# design.net
KiCad netlist of a schematic drawn in Altium Designer
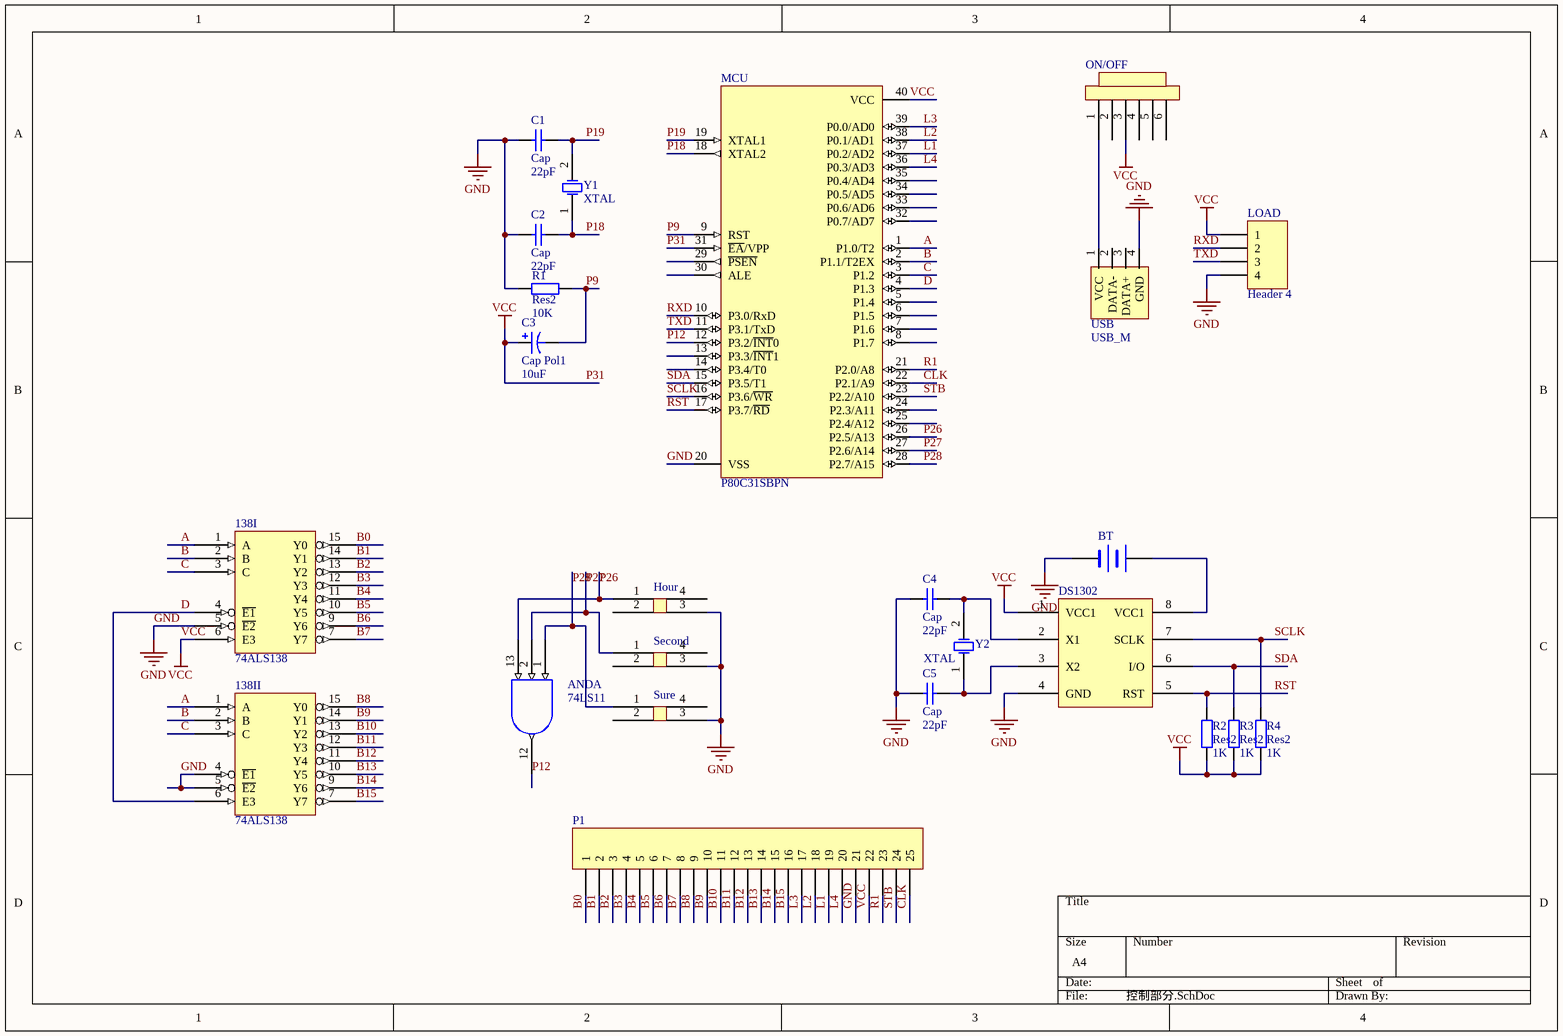
[diagram p0: 控制部分.SchDoc]

(export (version "E")
  (design (tool "Eeschema 10.0.6"))
  (components
    (comp (ref "138I")
      (value "74ALS138")
      (footprint "DIP-16")
      (libsource (lib "TTL74系列IC") (part "74ALS138"))
    )
    (comp (ref "138II")
      (value "74ALS138")
      (footprint "DIP-16")
      (libsource (lib "TTL74系列IC") (part "74ALS138"))
    )
    (comp (ref "AND") (value "74LS11") (footprint "DIP-14") (libsource (lib "TTL74系列IC") (part "74LS11")))
    (comp (ref "BT")
      (value "~")
      (footprint "纽扣电池:PCBComponent_1")
      (description "Battery")
      (libsource (lib "电池及电源") (part "干电池"))
    )
    (comp (ref "C1")
      (value "Cap")
      (footprint "Miscellaneous Connectors:HDR1X2")
      (description "Capacitor")
      (fields (field (name "ALTIUM_VALUE") "22pF") (field (name "PUBLISHER") "Altium Limited"))
      (libsource (lib "Miscellaneous Devices") (part "Cap"))
    )
    (comp (ref "C2")
      (value "Cap")
      (footprint "Miscellaneous Connectors:HDR1X2")
      (description "Capacitor")
      (fields (field (name "ALTIUM_VALUE") "22pF") (field (name "PUBLISHER") "Altium Limited"))
      (libsource (lib "Miscellaneous Devices") (part "Cap"))
    )
    (comp (ref "C3")
      (value "Cap Pol1")
      (footprint "单片机最小系统:LED")
      (description "Polarized Capacitor (Radial)")
      (fields (field (name "ALTIUM_VALUE") "10uF") (field (name "PUBLISHER") "Altium Limited"))
      (libsource (lib "Miscellaneous Devices") (part "Cap Pol1"))
    )
    (comp (ref "C4")
      (value "Cap")
      (footprint "PIN2")
      (description "Capacitor")
      (fields (field (name "ALTIUM_VALUE") "22pF") (field (name "PUBLISHER") "Altium Limited"))
      (libsource (lib "Miscellaneous Devices") (part "Cap"))
    )
    (comp (ref "C5")
      (value "Cap")
      (footprint "PIN2")
      (description "Capacitor")
      (fields (field (name "ALTIUM_VALUE") "22pF") (field (name "PUBLISHER") "Altium Limited"))
      (libsource (lib "Miscellaneous Devices") (part "Cap"))
    )
    (comp (ref "DS1302") (value "~") (footprint "DIP8") (libsource (lib "DS1302") (part "Component_1")))
    (comp (ref "Hour")
      (value "~")
      (footprint "按键1:PCBComponent_1")
      (libsource (lib "按键1") (part "Component_1"))
    )
    (comp (ref "LOAD")
      (value "Header 4")
      (footprint "HDR1X4")
      (description "Header, 4-Pin")
      (fields (field (name "PUBLISHER") "Altium Limited"))
      (libsource (lib "Miscellaneous Connectors") (part "Header 4"))
    )
    (comp (ref "MCU")
      (value "P80C31SBPN")
      (footprint "SOT129-1")
      (description "80C51 8-Bit Microcontroller Family: 128 B RAM, ROMless, 2.7 V-5.5 V, Low Power, High Speed")
      (fields (field (name "PUBLISHER") "Altium Limited"))
      (libsource (lib "Philips Microcontroller 8-Bit") (part "P80C31SBPN"))
    )
    (comp (ref "ON/OFF") (value "~") (footprint "复位开关:PCBComponent_1") (libsource (lib "复位开关") (part "复位开关")))
    (comp (ref "P1")
      (value "~")
      (footprint "HDR1X25")
      (description "Header, 25-Pin")
      (fields (field (name "PUBLISHER") "Altium Limited"))
      (libsource (lib "Miscellaneous Connectors") (part "Header 25"))
    )
    (comp (ref "R1")
      (value "Res2")
      (footprint "AXIAL-0.4")
      (description "Resistor")
      (fields (field (name "ALTIUM_VALUE") "10K") (field (name "PUBLISHER") "Altium Limited"))
      (libsource (lib "Miscellaneous Devices") (part "Res2"))
    )
    (comp (ref "R2")
      (value "Res2")
      (footprint "AXIAL-0.4")
      (description "Resistor")
      (fields (field (name "ALTIUM_VALUE") "1K") (field (name "PUBLISHER") "Altium Limited"))
      (libsource (lib "") (part "Res2_1"))
    )
    (comp (ref "R3")
      (value "Res2")
      (footprint "AXIAL-0.4")
      (description "Resistor")
      (fields (field (name "ALTIUM_VALUE") "1K") (field (name "PUBLISHER") "Altium Limited"))
      (libsource (lib "") (part "Res2_1"))
    )
    (comp (ref "R4")
      (value "Res2")
      (footprint "AXIAL-0.4")
      (description "Resistor")
      (fields (field (name "ALTIUM_VALUE") "1K") (field (name "PUBLISHER") "Altium Limited"))
      (libsource (lib "") (part "Res2_1"))
    )
    (comp (ref "Second")
      (value "~")
      (footprint "按键1:PCBComponent_1")
      (libsource (lib "按键1") (part "Component_1"))
    )
    (comp (ref "Sure")
      (value "~")
      (footprint "按键1:PCBComponent_1")
      (libsource (lib "按键1") (part "Component_1"))
    )
    (comp (ref "USB") (value "USB_M") (footprint "USB") (libsource (lib "SCH封装库") (part "USB_M")))
    (comp (ref "Y1")
      (value "XTAL")
      (footprint "晶振:PCBComponent_1")
      (description "Crystal Oscillator")
      (fields (field (name "PUBLISHER") "Altium Limited"))
      (libsource (lib "Miscellaneous Devices") (part "XTAL"))
    )
    (comp (ref "Y2")
      (value "XTAL")
      (footprint "HDR1X2")
      (description "Crystal Oscillator")
      (fields (field (name "PUBLISHER") "Altium Limited"))
      (libsource (lib "Miscellaneous Devices") (part "XTAL"))
    )
  )
  (nets
    (net (code "1") (name "/A") (class "Default")
      (node (ref "138I") (pin "1") (pinfunction "A_1") (pintype "input"))
      (node (ref "138II") (pin "1") (pinfunction "A_1") (pintype "input"))
      (node (ref "MCU") (pin "1") (pinfunction "P1.0/T2_1") (pintype "bidirectional"))
    )
    (net (code "2") (name "/B") (class "Default")
      (node (ref "138I") (pin "2") (pinfunction "B_2") (pintype "input"))
      (node (ref "138II") (pin "2") (pinfunction "B_2") (pintype "input"))
      (node (ref "MCU") (pin "2") (pinfunction "P1.1/T2EX_2") (pintype "bidirectional"))
    )
    (net (code "3") (name "/B0") (class "Default")
      (node (ref "138I") (pin "15") (pinfunction "Y0_15") (pintype "output"))
      (node (ref "P1") (pin "1") (pinfunction "1_1") (pintype "passive"))
    )
    (net (code "4") (name "/B1") (class "Default")
      (node (ref "138I") (pin "14") (pinfunction "Y1_14") (pintype "output"))
      (node (ref "P1") (pin "2") (pinfunction "2_2") (pintype "passive"))
    )
    (net (code "5") (name "/B2") (class "Default")
      (node (ref "138I") (pin "13") (pinfunction "Y2_13") (pintype "output"))
      (node (ref "P1") (pin "3") (pinfunction "3_3") (pintype "passive"))
    )
    (net (code "6") (name "/B3") (class "Default")
      (node (ref "138I") (pin "12") (pinfunction "Y3_12") (pintype "output"))
      (node (ref "P1") (pin "4") (pinfunction "4_4") (pintype "passive"))
    )
    (net (code "7") (name "/B4") (class "Default")
      (node (ref "138I") (pin "11") (pinfunction "Y4_11") (pintype "output"))
      (node (ref "P1") (pin "5") (pinfunction "5_5") (pintype "passive"))
    )
    (net (code "8") (name "/B5") (class "Default")
      (node (ref "138I") (pin "10") (pinfunction "Y5_10") (pintype "output"))
      (node (ref "P1") (pin "6") (pinfunction "6_6") (pintype "passive"))
    )
    (net (code "9") (name "/B6") (class "Default")
      (node (ref "138I") (pin "9") (pinfunction "Y6_9") (pintype "output"))
      (node (ref "P1") (pin "7") (pinfunction "7_7") (pintype "passive"))
    )
    (net (code "10") (name "/B7") (class "Default")
      (node (ref "138I") (pin "7") (pinfunction "Y7_7") (pintype "output"))
      (node (ref "P1") (pin "8") (pinfunction "8_8") (pintype "passive"))
    )
    (net (code "11") (name "/B8") (class "Default")
      (node (ref "138II") (pin "15") (pinfunction "Y0_15") (pintype "output"))
      (node (ref "P1") (pin "9") (pinfunction "9_9") (pintype "passive"))
    )
    (net (code "12") (name "/B9") (class "Default")
      (node (ref "138II") (pin "14") (pinfunction "Y1_14") (pintype "output"))
      (node (ref "P1") (pin "10") (pinfunction "10_10") (pintype "passive"))
    )
    (net (code "13") (name "/B10") (class "Default")
      (node (ref "138II") (pin "13") (pinfunction "Y2_13") (pintype "output"))
      (node (ref "P1") (pin "11") (pinfunction "11_11") (pintype "passive"))
    )
    (net (code "14") (name "/B11") (class "Default")
      (node (ref "138II") (pin "12") (pinfunction "Y3_12") (pintype "output"))
      (node (ref "P1") (pin "12") (pinfunction "12_12") (pintype "passive"))
    )
    (net (code "15") (name "/B12") (class "Default")
      (node (ref "138II") (pin "11") (pinfunction "Y4_11") (pintype "output"))
      (node (ref "P1") (pin "13") (pinfunction "13_13") (pintype "passive"))
    )
    (net (code "16") (name "/B13") (class "Default")
      (node (ref "138II") (pin "10") (pinfunction "Y5_10") (pintype "output"))
      (node (ref "P1") (pin "14") (pinfunction "14_14") (pintype "passive"))
    )
    (net (code "17") (name "/B14") (class "Default")
      (node (ref "138II") (pin "9") (pinfunction "Y6_9") (pintype "output"))
      (node (ref "P1") (pin "15") (pinfunction "15_15") (pintype "passive"))
    )
    (net (code "18") (name "/B15") (class "Default")
      (node (ref "138II") (pin "7") (pinfunction "Y7_7") (pintype "output"))
      (node (ref "P1") (pin "16") (pinfunction "16_16") (pintype "passive"))
    )
    (net (code "19") (name "/C") (class "Default")
      (node (ref "138I") (pin "3") (pinfunction "C_3") (pintype "input"))
      (node (ref "138II") (pin "3") (pinfunction "C_3") (pintype "input"))
      (node (ref "MCU") (pin "3") (pinfunction "P1.2_3") (pintype "bidirectional"))
    )
    (net (code "20") (name "/CLK") (class "Default")
      (node (ref "MCU") (pin "22") (pinfunction "P2.1/A9_22") (pintype "bidirectional"))
      (node (ref "P1") (pin "25") (pinfunction "25_25") (pintype "passive"))
    )
    (net (code "21") (name "/D") (class "Default")
      (node (ref "138I") (pin "4") (pinfunction "~{E1}_4") (pintype "input"))
      (node (ref "138II") (pin "6") (pinfunction "E3_6") (pintype "input"))
      (node (ref "MCU") (pin "4") (pinfunction "P1.3_4") (pintype "bidirectional"))
    )
    (net (code "22") (name "/L1") (class "Default")
      (node (ref "MCU") (pin "37") (pinfunction "P0.2/AD2_37") (pintype "bidirectional"))
      (node (ref "P1") (pin "19") (pinfunction "19_19") (pintype "passive"))
    )
    (net (code "23") (name "/L2") (class "Default")
      (node (ref "MCU") (pin "38") (pinfunction "P0.1/AD1_38") (pintype "bidirectional"))
      (node (ref "P1") (pin "18") (pinfunction "18_18") (pintype "passive"))
    )
    (net (code "24") (name "/L3") (class "Default")
      (node (ref "MCU") (pin "39") (pinfunction "P0.0/AD0_39") (pintype "bidirectional"))
      (node (ref "P1") (pin "17") (pinfunction "17_17") (pintype "passive"))
    )
    (net (code "25") (name "/L4") (class "Default")
      (node (ref "MCU") (pin "36") (pinfunction "P0.3/AD3_36") (pintype "bidirectional"))
      (node (ref "P1") (pin "20") (pinfunction "20_20") (pintype "passive"))
    )
    (net (code "26") (name "/P9") (class "Default")
      (node (ref "C3") (pin "2") (pinfunction "2_2") (pintype "passive"))
      (node (ref "MCU") (pin "9") (pinfunction "RST_9") (pintype "input"))
      (node (ref "R1") (pin "2") (pinfunction "2_2") (pintype "passive"))
    )
    (net (code "27") (name "/P12") (class "Default")
      (node (ref "AND") (pin "12") (pintype "output"))
      (node (ref "MCU") (pin "12") (pinfunction "P3.2/~{INT}0_12") (pintype "bidirectional"))
    )
    (net (code "28") (name "/P18") (class "Default")
      (node (ref "C2") (pin "2") (pinfunction "2_2") (pintype "passive"))
      (node (ref "MCU") (pin "18") (pinfunction "XTAL2_18") (pintype "output"))
      (node (ref "Y1") (pin "1") (pinfunction "OSC1_1") (pintype "passive"))
    )
    (net (code "29") (name "/P19") (class "Default")
      (node (ref "C1") (pin "2") (pinfunction "2_2") (pintype "passive"))
      (node (ref "MCU") (pin "19") (pinfunction "XTAL1_19") (pintype "input"))
      (node (ref "Y1") (pin "2") (pinfunction "OSC2_2") (pintype "passive"))
    )
    (net (code "30") (name "/P26") (class "Default")
      (node (ref "AND") (pin "13") (pintype "input"))
      (node (ref "Hour") (pin "1") (pintype "passive"))
      (node (ref "MCU") (pin "26") (pinfunction "P2.5/A13_26") (pintype "bidirectional"))
    )
    (net (code "31") (name "/P27") (class "Default")
      (node (ref "AND") (pin "2") (pintype "input"))
      (node (ref "MCU") (pin "27") (pinfunction "P2.6/A14_27") (pintype "bidirectional"))
      (node (ref "Second") (pin "1") (pintype "passive"))
    )
    (net (code "32") (name "/P28") (class "Default")
      (node (ref "AND") (pin "1") (pintype "input"))
      (node (ref "MCU") (pin "28") (pinfunction "P2.7/A15_28") (pintype "bidirectional"))
      (node (ref "Sure") (pin "1") (pintype "passive"))
    )
    (net (code "33") (name "/R1") (class "Default")
      (node (ref "MCU") (pin "21") (pinfunction "P2.0/A8_21") (pintype "bidirectional"))
      (node (ref "P1") (pin "23") (pinfunction "23_23") (pintype "passive"))
    )
    (net (code "34") (name "/RST") (class "Default")
      (node (ref "DS1302") (pin "5") (pinfunction "RST_5") (pintype "passive"))
      (node (ref "MCU") (pin "17") (pinfunction "P3.7/~{RD}_17") (pintype "bidirectional"))
      (node (ref "R2") (pin "2") (pinfunction "2_2") (pintype "passive"))
    )
    (net (code "35") (name "/RXD") (class "Default")
      (node (ref "LOAD") (pin "2") (pinfunction "2_2") (pintype "passive"))
      (node (ref "MCU") (pin "10") (pinfunction "P3.0/RxD_10") (pintype "bidirectional"))
    )
    (net (code "36") (name "/SCLK") (class "Default")
      (node (ref "DS1302") (pin "7") (pinfunction "SCLK_7") (pintype "passive"))
      (node (ref "MCU") (pin "16") (pinfunction "P3.6/~{WR}_16") (pintype "bidirectional"))
      (node (ref "R4") (pin "2") (pinfunction "2_2") (pintype "passive"))
    )
    (net (code "37") (name "/SDA") (class "Default")
      (node (ref "DS1302") (pin "6") (pinfunction "I/O_6") (pintype "passive"))
      (node (ref "MCU") (pin "15") (pinfunction "P3.5/T1_15") (pintype "bidirectional"))
      (node (ref "R3") (pin "2") (pinfunction "2_2") (pintype "passive"))
    )
    (net (code "38") (name "/STB") (class "Default")
      (node (ref "MCU") (pin "23") (pinfunction "P2.2/A10_23") (pintype "bidirectional"))
      (node (ref "P1") (pin "24") (pinfunction "24_24") (pintype "passive"))
    )
    (net (code "39") (name "/TXD") (class "Default")
      (node (ref "LOAD") (pin "3") (pinfunction "3_3") (pintype "passive"))
      (node (ref "MCU") (pin "11") (pinfunction "P3.1/TxD_11") (pintype "bidirectional"))
    )
    (net (code "40") (name "GND") (class "Default")
      (node (ref "138I") (pin "5") (pinfunction "~{E2}_5") (pintype "input"))
      (node (ref "138I") (pin "8") (pinfunction "GND_8") (pintype "power_in"))
      (node (ref "138II") (pin "4") (pinfunction "~{E1}_4") (pintype "input"))
      (node (ref "138II") (pin "5") (pinfunction "~{E2}_5") (pintype "input"))
      (node (ref "138II") (pin "8") (pinfunction "GND_8") (pintype "power_in"))
      (node (ref "AND") (pin "7") (pinfunction "GND_7") (pintype "power_in"))
      (node (ref "BT") (pin "2") (pinfunction "-_2") (pintype "passive"))
      (node (ref "C1") (pin "1") (pinfunction "1_1") (pintype "passive"))
      (node (ref "C2") (pin "1") (pinfunction "1_1") (pintype "passive"))
      (node (ref "C4") (pin "1") (pinfunction "1_1") (pintype "passive"))
      (node (ref "C5") (pin "1") (pinfunction "1_1") (pintype "passive"))
      (node (ref "DS1302") (pin "4") (pinfunction "GND_4") (pintype "passive"))
      (node (ref "Hour") (pin "3") (pintype "passive"))
      (node (ref "LOAD") (pin "4") (pinfunction "4_4") (pintype "passive"))
      (node (ref "MCU") (pin "20") (pinfunction "VSS_20") (pintype "power_in"))
      (node (ref "P1") (pin "21") (pinfunction "21_21") (pintype "passive"))
      (node (ref "R1") (pin "1") (pinfunction "1_1") (pintype "passive"))
      (node (ref "Second") (pin "3") (pintype "passive"))
      (node (ref "Sure") (pin "3") (pintype "passive"))
      (node (ref "USB") (pin "4") (pinfunction "GND_4") (pintype "passive"))
    )
    (net (code "41") (name "Net-(BT-+)") (class "Default")
      (node (ref "BT") (pin "1") (pinfunction "+_1") (pintype "passive"))
      (node (ref "DS1302") (pin "8") (pinfunction "VCC1_8") (pintype "passive"))
    )
    (net (code "42") (name "Net-(DS1302-X1)") (class "Default")
      (node (ref "C4") (pin "2") (pinfunction "2_2") (pintype "passive"))
      (node (ref "DS1302") (pin "2") (pinfunction "X1_2") (pintype "passive"))
      (node (ref "Y2") (pin "2") (pinfunction "OSC2_2") (pintype "passive"))
    )
    (net (code "43") (name "Net-(DS1302-X2)") (class "Default")
      (node (ref "C5") (pin "2") (pinfunction "2_2") (pintype "passive"))
      (node (ref "DS1302") (pin "3") (pinfunction "X2_3") (pintype "passive"))
      (node (ref "Y2") (pin "1") (pinfunction "OSC1_1") (pintype "passive"))
    )
    (net (code "44") (name "Net-(USB-VCC)") (class "Default")
      (node (ref "ON/OFF") (pin "1") (pintype "passive"))
      (node (ref "USB") (pin "1") (pinfunction "VCC_1") (pintype "passive"))
    )
    (net (code "45") (name "VCC") (class "Default")
      (node (ref "138I") (pin "16") (pinfunction "VCC_16") (pintype "power_in"))
      (node (ref "138I") (pin "6") (pinfunction "E3_6") (pintype "input"))
      (node (ref "138II") (pin "16") (pinfunction "VCC_16") (pintype "power_in"))
      (node (ref "AND") (pin "14") (pinfunction "VCC_14") (pintype "power_in"))
      (node (ref "C3") (pin "1") (pinfunction "1_1") (pintype "passive"))
      (node (ref "DS1302") (pin "1") (pinfunction "VCC1_1") (pintype "passive"))
      (node (ref "LOAD") (pin "1") (pinfunction "1_1") (pintype "passive"))
      (node (ref "MCU") (pin "31") (pinfunction "~{EA}/VPP_31") (pintype "input"))
      (node (ref "MCU") (pin "40") (pinfunction "VCC_40") (pintype "power_in"))
      (node (ref "ON/OFF") (pin "3") (pintype "passive"))
      (node (ref "P1") (pin "22") (pinfunction "22_22") (pintype "passive"))
      (node (ref "R2") (pin "1") (pinfunction "1_1") (pintype "passive"))
      (node (ref "R3") (pin "1") (pinfunction "1_1") (pintype "passive"))
      (node (ref "R4") (pin "1") (pinfunction "1_1") (pintype "passive"))
    )
    (net (code "46") (name "unconnected-(Hour-Pad2)") (class "Default")
      (node (ref "Hour") (pin "2") (pintype "passive"))
    )
    (net (code "47") (name "unconnected-(Hour-Pad4)") (class "Default")
      (node (ref "Hour") (pin "4") (pintype "passive"))
    )
    (net (code "48") (name "unconnected-(MCU-ALE-Pad30)") (class "Default")
      (node (ref "MCU") (pin "30") (pinfunction "ALE_30") (pintype "output"))
    )
    (net (code "49") (name "unconnected-(MCU-P0.4{slash}AD4-Pad35)") (class "Default")
      (node (ref "MCU") (pin "35") (pinfunction "P0.4/AD4_35") (pintype "bidirectional"))
    )
    (net (code "50") (name "unconnected-(MCU-P0.5{slash}AD5-Pad34)") (class "Default")
      (node (ref "MCU") (pin "34") (pinfunction "P0.5/AD5_34") (pintype "bidirectional"))
    )
    (net (code "51") (name "unconnected-(MCU-P0.6{slash}AD6-Pad33)") (class "Default")
      (node (ref "MCU") (pin "33") (pinfunction "P0.6/AD6_33") (pintype "bidirectional"))
    )
    (net (code "52") (name "unconnected-(MCU-P0.7{slash}AD7-Pad32)") (class "Default")
      (node (ref "MCU") (pin "32") (pinfunction "P0.7/AD7_32") (pintype "bidirectional"))
    )
    (net (code "53") (name "unconnected-(MCU-P1.4-Pad5)") (class "Default")
      (node (ref "MCU") (pin "5") (pinfunction "P1.4_5") (pintype "bidirectional"))
    )
    (net (code "54") (name "unconnected-(MCU-P1.5-Pad6)") (class "Default")
      (node (ref "MCU") (pin "6") (pinfunction "P1.5_6") (pintype "bidirectional"))
    )
    (net (code "55") (name "unconnected-(MCU-P1.6-Pad7)") (class "Default")
      (node (ref "MCU") (pin "7") (pinfunction "P1.6_7") (pintype "bidirectional"))
    )
    (net (code "56") (name "unconnected-(MCU-P1.7-Pad8)") (class "Default")
      (node (ref "MCU") (pin "8") (pinfunction "P1.7_8") (pintype "bidirectional"))
    )
    (net (code "57") (name "unconnected-(MCU-P2.3{slash}A11-Pad24)") (class "Default")
      (node (ref "MCU") (pin "24") (pinfunction "P2.3/A11_24") (pintype "bidirectional"))
    )
    (net (code "58") (name "unconnected-(MCU-P2.4{slash}A12-Pad25)") (class "Default")
      (node (ref "MCU") (pin "25") (pinfunction "P2.4/A12_25") (pintype "bidirectional"))
    )
    (net (code "59") (name "unconnected-(MCU-P3.3{slash}~{INT}1-Pad13)") (class "Default")
      (node (ref "MCU") (pin "13") (pinfunction "P3.3/~{INT}1_13") (pintype "bidirectional"))
    )
    (net (code "60") (name "unconnected-(MCU-P3.4{slash}T0-Pad14)") (class "Default")
      (node (ref "MCU") (pin "14") (pinfunction "P3.4/T0_14") (pintype "bidirectional"))
    )
    (net (code "61") (name "unconnected-(MCU-~{PSEN}-Pad29)") (class "Default")
      (node (ref "MCU") (pin "29") (pinfunction "~{PSEN}_29") (pintype "output"))
    )
    (net (code "62") (name "unconnected-(ON/OFF-Pad2)") (class "Default")
      (node (ref "ON/OFF") (pin "2") (pintype "passive"))
    )
    (net (code "63") (name "unconnected-(ON/OFF-Pad4)") (class "Default")
      (node (ref "ON/OFF") (pin "4") (pintype "passive"))
    )
    (net (code "64") (name "unconnected-(ON/OFF-Pad5)") (class "Default")
      (node (ref "ON/OFF") (pin "5") (pintype "passive"))
    )
    (net (code "65") (name "unconnected-(ON/OFF-Pad6)") (class "Default")
      (node (ref "ON/OFF") (pin "6") (pintype "passive"))
    )
    (net (code "66") (name "unconnected-(Second-Pad2)") (class "Default")
      (node (ref "Second") (pin "2") (pintype "passive"))
    )
    (net (code "67") (name "unconnected-(Second-Pad4)") (class "Default")
      (node (ref "Second") (pin "4") (pintype "passive"))
    )
    (net (code "68") (name "unconnected-(Sure-Pad2)") (class "Default")
      (node (ref "Sure") (pin "2") (pintype "passive"))
    )
    (net (code "69") (name "unconnected-(Sure-Pad4)") (class "Default")
      (node (ref "Sure") (pin "4") (pintype "passive"))
    )
    (net (code "70") (name "unconnected-(USB-DATA+-Pad3)") (class "Default")
      (node (ref "USB") (pin "3") (pinfunction "DATA+_3") (pintype "passive"))
    )
    (net (code "71") (name "unconnected-(USB-DATA--Pad2)") (class "Default")
      (node (ref "USB") (pin "2") (pinfunction "DATA-_2") (pintype "passive"))
    )
  )
)
